# x-OSC_Gloves_v2.net
KiCad netlist of a schematic drawn in EAGLE
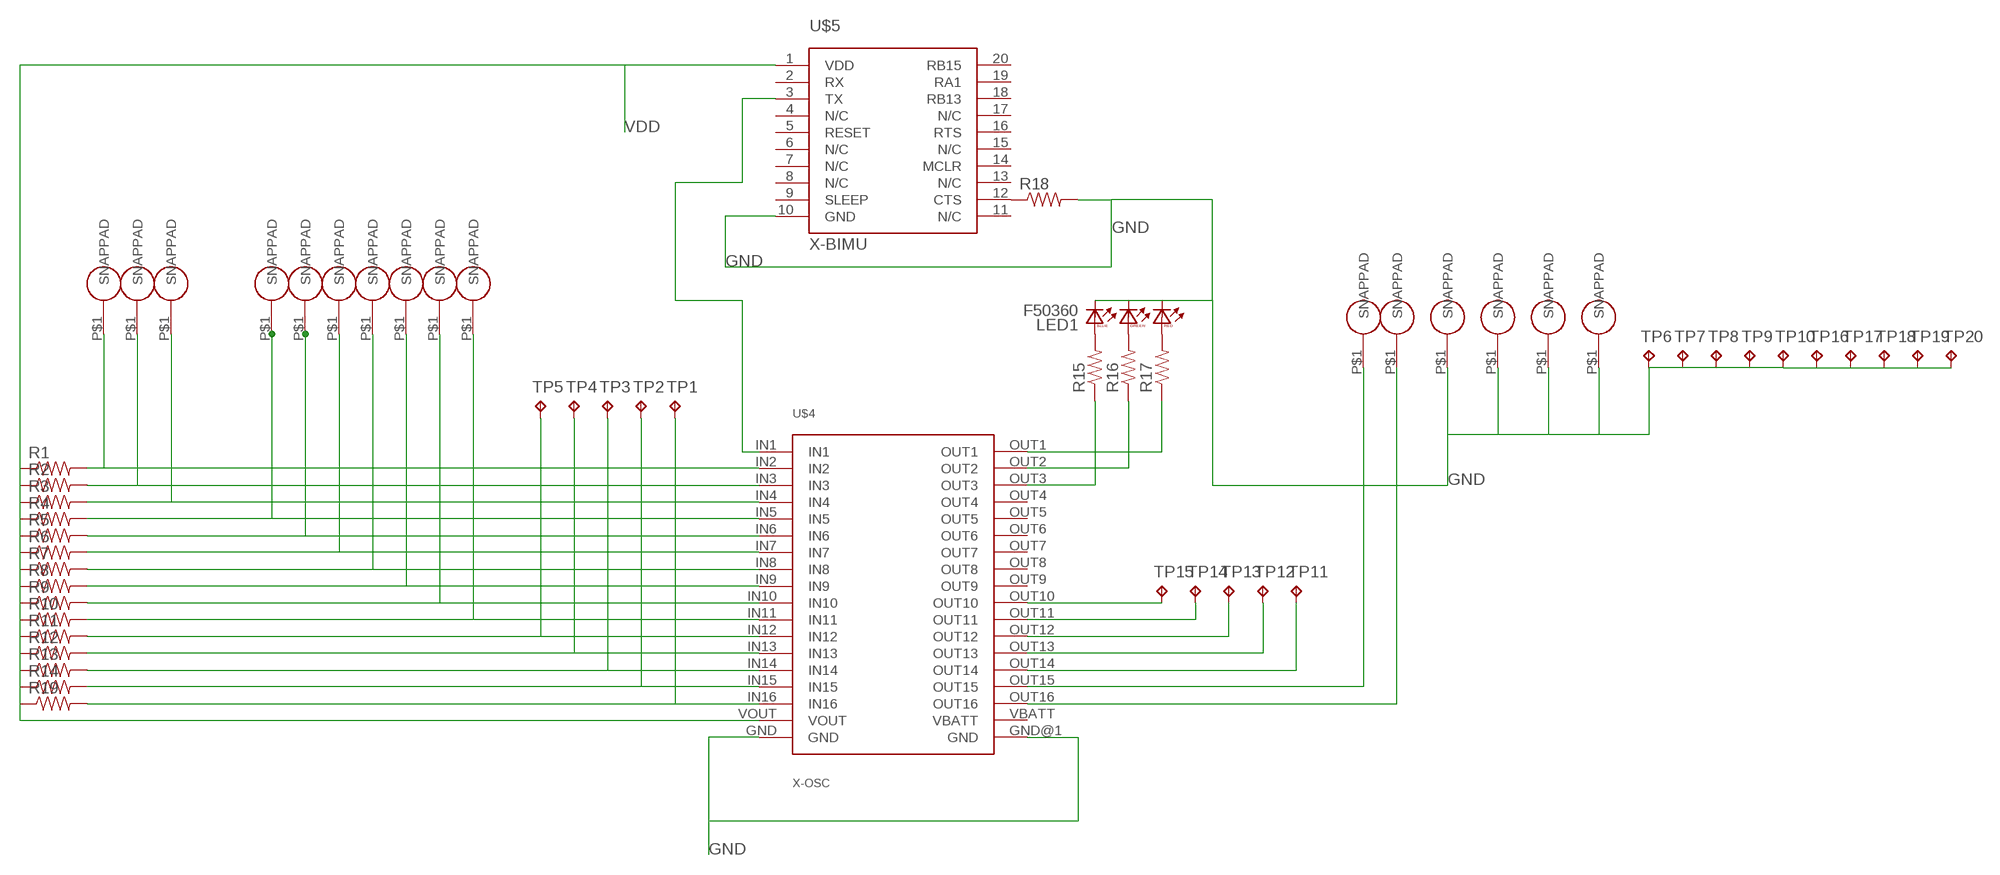
[diagram p0: schematic, sheet 1]

(export (version "E")
  (design (tool "Eeschema 10.0.6"))
  (components
    (comp (ref "LED1")
      (value "F50360")
      (footprint "eagle-import:F50360")
      (libsource (lib "eagle-import") (part "F50360"))
    )
    (comp (ref "R1")
      (value "RESISTOR0805-RES")
      (footprint "eagle-import:0805")
      (libsource (lib "eagle-import") (part "RESISTOR0805-RES"))
    )
    (comp (ref "R2")
      (value "RESISTOR0805-RES")
      (footprint "eagle-import:0805")
      (libsource (lib "eagle-import") (part "RESISTOR0805-RES"))
    )
    (comp (ref "R3")
      (value "RESISTOR0805-RES")
      (footprint "eagle-import:0805")
      (libsource (lib "eagle-import") (part "RESISTOR0805-RES"))
    )
    (comp (ref "R4")
      (value "RESISTOR0805-RES")
      (footprint "eagle-import:0805")
      (libsource (lib "eagle-import") (part "RESISTOR0805-RES"))
    )
    (comp (ref "R5")
      (value "RESISTOR0805-RES")
      (footprint "eagle-import:0805")
      (libsource (lib "eagle-import") (part "RESISTOR0805-RES"))
    )
    (comp (ref "R6")
      (value "RESISTOR0805-RES")
      (footprint "eagle-import:0805")
      (libsource (lib "eagle-import") (part "RESISTOR0805-RES"))
    )
    (comp (ref "R7")
      (value "RESISTOR0805-RES")
      (footprint "eagle-import:0805")
      (libsource (lib "eagle-import") (part "RESISTOR0805-RES"))
    )
    (comp (ref "R8")
      (value "RESISTOR0805-RES")
      (footprint "eagle-import:0805")
      (libsource (lib "eagle-import") (part "RESISTOR0805-RES"))
    )
    (comp (ref "R9")
      (value "RESISTOR0805-RES")
      (footprint "eagle-import:0805")
      (libsource (lib "eagle-import") (part "RESISTOR0805-RES"))
    )
    (comp (ref "R10")
      (value "RESISTOR0805-RES")
      (footprint "eagle-import:0805")
      (libsource (lib "eagle-import") (part "RESISTOR0805-RES"))
    )
    (comp (ref "R11")
      (value "RESISTOR0805-RES")
      (footprint "eagle-import:0805")
      (libsource (lib "eagle-import") (part "RESISTOR0805-RES"))
    )
    (comp (ref "R12")
      (value "RESISTOR0805-RES")
      (footprint "eagle-import:0805")
      (libsource (lib "eagle-import") (part "RESISTOR0805-RES"))
    )
    (comp (ref "R13")
      (value "RESISTOR0805-RES")
      (footprint "eagle-import:0805")
      (libsource (lib "eagle-import") (part "RESISTOR0805-RES"))
    )
    (comp (ref "R14")
      (value "RESISTOR0805-RES")
      (footprint "eagle-import:0805")
      (libsource (lib "eagle-import") (part "RESISTOR0805-RES"))
    )
    (comp (ref "R15")
      (value "RESISTOR0805-RES")
      (footprint "eagle-import:0805")
      (libsource (lib "eagle-import") (part "RESISTOR0805-RES"))
    )
    (comp (ref "R16")
      (value "RESISTOR0805-RES")
      (footprint "eagle-import:0805")
      (libsource (lib "eagle-import") (part "RESISTOR0805-RES"))
    )
    (comp (ref "R17")
      (value "RESISTOR0805-RES")
      (footprint "eagle-import:0805")
      (libsource (lib "eagle-import") (part "RESISTOR0805-RES"))
    )
    (comp (ref "R18")
      (value "RESISTOR0805-RES")
      (footprint "eagle-import:0805")
      (libsource (lib "eagle-import") (part "RESISTOR0805-RES"))
    )
    (comp (ref "R19")
      (value "RESISTOR0805-RES")
      (footprint "eagle-import:0805")
      (libsource (lib "eagle-import") (part "RESISTOR0805-RES"))
    )
    (comp (ref "TP1")
      (value "TPTP20R")
      (footprint "eagle-import:TP20R")
      (libsource (lib "eagle-import") (part "TPTP20R"))
    )
    (comp (ref "TP2")
      (value "TPTP20R")
      (footprint "eagle-import:TP20R")
      (libsource (lib "eagle-import") (part "TPTP20R"))
    )
    (comp (ref "TP3")
      (value "TPTP20R")
      (footprint "eagle-import:TP20R")
      (libsource (lib "eagle-import") (part "TPTP20R"))
    )
    (comp (ref "TP4")
      (value "TPTP20R")
      (footprint "eagle-import:TP20R")
      (libsource (lib "eagle-import") (part "TPTP20R"))
    )
    (comp (ref "TP5")
      (value "TPTP20R")
      (footprint "eagle-import:TP20R")
      (libsource (lib "eagle-import") (part "TPTP20R"))
    )
    (comp (ref "TP6")
      (value "TPTP20R")
      (footprint "eagle-import:TP20R")
      (libsource (lib "eagle-import") (part "TPTP20R"))
    )
    (comp (ref "TP7")
      (value "TPTP20R")
      (footprint "eagle-import:TP20R")
      (libsource (lib "eagle-import") (part "TPTP20R"))
    )
    (comp (ref "TP8")
      (value "TPTP20R")
      (footprint "eagle-import:TP20R")
      (libsource (lib "eagle-import") (part "TPTP20R"))
    )
    (comp (ref "TP9")
      (value "TPTP20R")
      (footprint "eagle-import:TP20R")
      (libsource (lib "eagle-import") (part "TPTP20R"))
    )
    (comp (ref "TP10")
      (value "TPTP20R")
      (footprint "eagle-import:TP20R")
      (libsource (lib "eagle-import") (part "TPTP20R"))
    )
    (comp (ref "TP11")
      (value "TPTP20R")
      (footprint "eagle-import:TP20R")
      (libsource (lib "eagle-import") (part "TPTP20R"))
    )
    (comp (ref "TP12")
      (value "TPTP20R")
      (footprint "eagle-import:TP20R")
      (libsource (lib "eagle-import") (part "TPTP20R"))
    )
    (comp (ref "TP13")
      (value "TPTP20R")
      (footprint "eagle-import:TP20R")
      (libsource (lib "eagle-import") (part "TPTP20R"))
    )
    (comp (ref "TP14")
      (value "TPTP20R")
      (footprint "eagle-import:TP20R")
      (libsource (lib "eagle-import") (part "TPTP20R"))
    )
    (comp (ref "TP15")
      (value "TPTP20R")
      (footprint "eagle-import:TP20R")
      (libsource (lib "eagle-import") (part "TPTP20R"))
    )
    (comp (ref "TP16")
      (value "TPTP20R")
      (footprint "eagle-import:TP20R")
      (libsource (lib "eagle-import") (part "TPTP20R"))
    )
    (comp (ref "TP17")
      (value "TPTP20R")
      (footprint "eagle-import:TP20R")
      (libsource (lib "eagle-import") (part "TPTP20R"))
    )
    (comp (ref "TP18")
      (value "TPTP20R")
      (footprint "eagle-import:TP20R")
      (libsource (lib "eagle-import") (part "TPTP20R"))
    )
    (comp (ref "TP19")
      (value "TPTP20R")
      (footprint "eagle-import:TP20R")
      (libsource (lib "eagle-import") (part "TPTP20R"))
    )
    (comp (ref "TP20")
      (value "TPTP20R")
      (footprint "eagle-import:TP20R")
      (libsource (lib "eagle-import") (part "TPTP20R"))
    )
    (comp (ref "U$1")
      (value "SNAP-PAD_7MM_ROUND")
      (footprint "eagle-import:SNAP-PAD_7MM_RD")
      (libsource (lib "eagle-import") (part "SNAP-PAD_7MM_ROUND"))
    )
    (comp (ref "U$2")
      (value "SNAP-PAD_7MM_ROUND")
      (footprint "eagle-import:SNAP-PAD_7MM_RD")
      (libsource (lib "eagle-import") (part "SNAP-PAD_7MM_ROUND"))
    )
    (comp (ref "U$3")
      (value "SNAP-PAD_7MM_ROUND")
      (footprint "eagle-import:SNAP-PAD_7MM_RD")
      (libsource (lib "eagle-import") (part "SNAP-PAD_7MM_ROUND"))
    )
    (comp (ref "U$4")
      (value "X-OSC")
      (footprint "eagle-import:X-OSC_SMD")
      (libsource (lib "eagle-import") (part "X-OSC"))
    )
    (comp (ref "U$5")
      (value "X-BIMU")
      (footprint "eagle-import:X-BIMU_SMD")
      (libsource (lib "eagle-import") (part "X-BIMU"))
    )
    (comp (ref "U$6")
      (value "SNAP-PAD_7MM_ROUND")
      (footprint "eagle-import:SNAP-PAD_7MM_RD")
      (libsource (lib "eagle-import") (part "SNAP-PAD_7MM_ROUND"))
    )
    (comp (ref "U$7")
      (value "SNAP-PAD_7MM_ROUND")
      (footprint "eagle-import:SNAP-PAD_7MM_RD")
      (libsource (lib "eagle-import") (part "SNAP-PAD_7MM_ROUND"))
    )
    (comp (ref "U$8")
      (value "SNAP-PAD_7MM_ROUND")
      (footprint "eagle-import:SNAP-PAD_7MM_RD")
      (libsource (lib "eagle-import") (part "SNAP-PAD_7MM_ROUND"))
    )
    (comp (ref "U$9")
      (value "SNAP-PAD_7MM_ROUND")
      (footprint "eagle-import:SNAP-PAD_7MM_RD")
      (libsource (lib "eagle-import") (part "SNAP-PAD_7MM_ROUND"))
    )
    (comp (ref "U$10")
      (value "SNAP-PAD_7MM_ROUND")
      (footprint "eagle-import:SNAP-PAD_7MM_RD")
      (libsource (lib "eagle-import") (part "SNAP-PAD_7MM_ROUND"))
    )
    (comp (ref "U$11")
      (value "SNAP-PAD_7MM_ROUND")
      (footprint "eagle-import:SNAP-PAD_7MM_RD")
      (libsource (lib "eagle-import") (part "SNAP-PAD_7MM_ROUND"))
    )
    (comp (ref "U$12")
      (value "SNAP-PAD_7MM_ROUND")
      (footprint "eagle-import:SNAP-PAD_7MM_RD")
      (libsource (lib "eagle-import") (part "SNAP-PAD_7MM_ROUND"))
    )
    (comp (ref "U$13")
      (value "SNAP-PAD_7MM_ROUND")
      (footprint "eagle-import:SNAP-PAD_7MM_RD")
      (libsource (lib "eagle-import") (part "SNAP-PAD_7MM_ROUND"))
    )
    (comp (ref "U$14")
      (value "SNAP-PAD_7MM_ROUND")
      (footprint "eagle-import:SNAP-PAD_7MM_RD")
      (libsource (lib "eagle-import") (part "SNAP-PAD_7MM_ROUND"))
    )
    (comp (ref "U$15")
      (value "SNAP-PAD_7MM_ROUND")
      (footprint "eagle-import:SNAP-PAD_7MM_RD")
      (libsource (lib "eagle-import") (part "SNAP-PAD_7MM_ROUND"))
    )
    (comp (ref "U$16")
      (value "SNAP-PAD_7MM_ROUND")
      (footprint "eagle-import:SNAP-PAD_7MM_RD")
      (libsource (lib "eagle-import") (part "SNAP-PAD_7MM_ROUND"))
    )
    (comp (ref "U$17")
      (value "SNAP-PAD_7MM_ROUND")
      (footprint "eagle-import:SNAP-PAD_7MM_RD")
      (libsource (lib "eagle-import") (part "SNAP-PAD_7MM_ROUND"))
    )
    (comp (ref "U$18")
      (value "SNAP-PAD_7MM_ROUND")
      (footprint "eagle-import:SNAP-PAD_7MM_RD")
      (libsource (lib "eagle-import") (part "SNAP-PAD_7MM_ROUND"))
    )
  )
  (nets
    (net (code "1") (name "/GND") (class "Default")
      (node (ref "LED1") (pin "BC") (pinfunction "BC_BC") (pintype "passive"))
      (node (ref "LED1") (pin "GC") (pinfunction "GC_GC") (pintype "passive"))
      (node (ref "LED1") (pin "RC") (pinfunction "RC_RC") (pintype "passive"))
      (node (ref "R18") (pin "2") (pinfunction "2_2") (pintype "passive"))
      (node (ref "TP10") (pin "TP") (pinfunction "TP_TP") (pintype "input"))
      (node (ref "TP16") (pin "TP") (pinfunction "TP_TP") (pintype "input"))
      (node (ref "TP17") (pin "TP") (pinfunction "TP_TP") (pintype "input"))
      (node (ref "TP18") (pin "TP") (pinfunction "TP_TP") (pintype "input"))
      (node (ref "TP19") (pin "TP") (pinfunction "TP_TP") (pintype "input"))
      (node (ref "TP20") (pin "TP") (pinfunction "TP_TP") (pintype "input"))
      (node (ref "TP6") (pin "TP") (pinfunction "TP_TP") (pintype "input"))
      (node (ref "TP7") (pin "TP") (pinfunction "TP_TP") (pintype "input"))
      (node (ref "TP8") (pin "TP") (pinfunction "TP_TP") (pintype "input"))
      (node (ref "TP9") (pin "TP") (pinfunction "TP_TP") (pintype "input"))
      (node (ref "U$15") (pin "P$1") (pinfunction "SNAPPAD_P$1") (pintype "bidirectional"))
      (node (ref "U$16") (pin "P$1") (pinfunction "SNAPPAD_P$1") (pintype "bidirectional"))
      (node (ref "U$17") (pin "P$1") (pinfunction "SNAPPAD_P$1") (pintype "bidirectional"))
      (node (ref "U$18") (pin "P$1") (pinfunction "SNAPPAD_P$1") (pintype "bidirectional"))
      (node (ref "U$4") (pin "GND") (pinfunction "GND_GND") (pintype "bidirectional"))
      (node (ref "U$4") (pin "GND@1") (pinfunction "GND_GND@1") (pintype "bidirectional"))
      (node (ref "U$5") (pin "10") (pinfunction "GND_10") (pintype "bidirectional"))
    )
    (net (code "2") (name "/VDD") (class "Default")
      (node (ref "R1") (pin "1") (pinfunction "1_1") (pintype "passive"))
      (node (ref "R10") (pin "1") (pinfunction "1_1") (pintype "passive"))
      (node (ref "R11") (pin "1") (pinfunction "1_1") (pintype "passive"))
      (node (ref "R12") (pin "1") (pinfunction "1_1") (pintype "passive"))
      (node (ref "R13") (pin "1") (pinfunction "1_1") (pintype "passive"))
      (node (ref "R14") (pin "1") (pinfunction "1_1") (pintype "passive"))
      (node (ref "R19") (pin "1") (pinfunction "1_1") (pintype "passive"))
      (node (ref "R2") (pin "1") (pinfunction "1_1") (pintype "passive"))
      (node (ref "R3") (pin "1") (pinfunction "1_1") (pintype "passive"))
      (node (ref "R4") (pin "1") (pinfunction "1_1") (pintype "passive"))
      (node (ref "R5") (pin "1") (pinfunction "1_1") (pintype "passive"))
      (node (ref "R6") (pin "1") (pinfunction "1_1") (pintype "passive"))
      (node (ref "R7") (pin "1") (pinfunction "1_1") (pintype "passive"))
      (node (ref "R8") (pin "1") (pinfunction "1_1") (pintype "passive"))
      (node (ref "R9") (pin "1") (pinfunction "1_1") (pintype "passive"))
      (node (ref "U$4") (pin "VOUT") (pinfunction "VOUT_VOUT") (pintype "bidirectional"))
      (node (ref "U$5") (pin "1") (pinfunction "VDD_1") (pintype "bidirectional"))
    )
    (net (code "3") (name "Net-(LED1-PadBA)") (class "Default")
      (node (ref "LED1") (pin "BA") (pinfunction "BA_BA") (pintype "passive"))
      (node (ref "R15") (pin "2") (pinfunction "2_2") (pintype "passive"))
    )
    (net (code "4") (name "Net-(LED1-PadGA)") (class "Default")
      (node (ref "LED1") (pin "GA") (pinfunction "GA_GA") (pintype "passive"))
      (node (ref "R16") (pin "2") (pinfunction "2_2") (pintype "passive"))
    )
    (net (code "5") (name "Net-(LED1-PadRA)") (class "Default")
      (node (ref "LED1") (pin "RA") (pinfunction "RA_RA") (pintype "passive"))
      (node (ref "R17") (pin "2") (pinfunction "2_2") (pintype "passive"))
    )
    (net (code "6") (name "Net-(R11-Pad2)") (class "Default")
      (node (ref "R11") (pin "2") (pinfunction "2_2") (pintype "passive"))
      (node (ref "TP5") (pin "TP") (pinfunction "TP_TP") (pintype "input"))
      (node (ref "U$4") (pin "IN12") (pinfunction "IN12_IN12") (pintype "bidirectional"))
    )
    (net (code "7") (name "Net-(R12-Pad2)") (class "Default")
      (node (ref "R12") (pin "2") (pinfunction "2_2") (pintype "passive"))
      (node (ref "TP4") (pin "TP") (pinfunction "TP_TP") (pintype "input"))
      (node (ref "U$4") (pin "IN13") (pinfunction "IN13_IN13") (pintype "bidirectional"))
    )
    (net (code "8") (name "Net-(R13-Pad2)") (class "Default")
      (node (ref "R13") (pin "2") (pinfunction "2_2") (pintype "passive"))
      (node (ref "TP3") (pin "TP") (pinfunction "TP_TP") (pintype "input"))
      (node (ref "U$4") (pin "IN14") (pinfunction "IN14_IN14") (pintype "bidirectional"))
    )
    (net (code "9") (name "Net-(R14-Pad2)") (class "Default")
      (node (ref "R14") (pin "2") (pinfunction "2_2") (pintype "passive"))
      (node (ref "TP2") (pin "TP") (pinfunction "TP_TP") (pintype "input"))
      (node (ref "U$4") (pin "IN15") (pinfunction "IN15_IN15") (pintype "bidirectional"))
    )
    (net (code "10") (name "Net-(R15-Pad1)") (class "Default")
      (node (ref "R15") (pin "1") (pinfunction "1_1") (pintype "passive"))
      (node (ref "U$4") (pin "OUT3") (pinfunction "OUT3_OUT3") (pintype "bidirectional"))
    )
    (net (code "11") (name "Net-(R16-Pad1)") (class "Default")
      (node (ref "R16") (pin "1") (pinfunction "1_1") (pintype "passive"))
      (node (ref "U$4") (pin "OUT2") (pinfunction "OUT2_OUT2") (pintype "bidirectional"))
    )
    (net (code "12") (name "Net-(R17-Pad1)") (class "Default")
      (node (ref "R17") (pin "1") (pinfunction "1_1") (pintype "passive"))
      (node (ref "U$4") (pin "OUT1") (pinfunction "OUT1_OUT1") (pintype "bidirectional"))
    )
    (net (code "13") (name "Net-(R19-Pad2)") (class "Default")
      (node (ref "R19") (pin "2") (pinfunction "2_2") (pintype "passive"))
      (node (ref "TP1") (pin "TP") (pinfunction "TP_TP") (pintype "input"))
      (node (ref "U$4") (pin "IN16") (pinfunction "IN16_IN16") (pintype "bidirectional"))
    )
    (net (code "14") (name "Net-(TP11-PadTP)") (class "Default")
      (node (ref "TP11") (pin "TP") (pinfunction "TP_TP") (pintype "input"))
      (node (ref "U$4") (pin "OUT14") (pinfunction "OUT14_OUT14") (pintype "bidirectional"))
    )
    (net (code "15") (name "Net-(TP12-PadTP)") (class "Default")
      (node (ref "TP12") (pin "TP") (pinfunction "TP_TP") (pintype "input"))
      (node (ref "U$4") (pin "OUT13") (pinfunction "OUT13_OUT13") (pintype "bidirectional"))
    )
    (net (code "16") (name "Net-(TP13-PadTP)") (class "Default")
      (node (ref "TP13") (pin "TP") (pinfunction "TP_TP") (pintype "input"))
      (node (ref "U$4") (pin "OUT12") (pinfunction "OUT12_OUT12") (pintype "bidirectional"))
    )
    (net (code "17") (name "Net-(TP14-PadTP)") (class "Default")
      (node (ref "TP14") (pin "TP") (pinfunction "TP_TP") (pintype "input"))
      (node (ref "U$4") (pin "OUT11") (pinfunction "OUT11_OUT11") (pintype "bidirectional"))
    )
    (net (code "18") (name "Net-(TP15-PadTP)") (class "Default")
      (node (ref "TP15") (pin "TP") (pinfunction "TP_TP") (pintype "input"))
      (node (ref "U$4") (pin "OUT10") (pinfunction "OUT10_OUT10") (pintype "bidirectional"))
    )
    (net (code "19") (name "Net-(U$1-SNAPPAD)") (class "Default")
      (node (ref "R1") (pin "2") (pinfunction "2_2") (pintype "passive"))
      (node (ref "U$1") (pin "P$1") (pinfunction "SNAPPAD_P$1") (pintype "bidirectional"))
      (node (ref "U$4") (pin "IN2") (pinfunction "IN2_IN2") (pintype "bidirectional"))
    )
    (net (code "20") (name "Net-(U$2-SNAPPAD)") (class "Default")
      (node (ref "R2") (pin "2") (pinfunction "2_2") (pintype "passive"))
      (node (ref "U$2") (pin "P$1") (pinfunction "SNAPPAD_P$1") (pintype "bidirectional"))
      (node (ref "U$4") (pin "IN3") (pinfunction "IN3_IN3") (pintype "bidirectional"))
    )
    (net (code "21") (name "Net-(U$3-SNAPPAD)") (class "Default")
      (node (ref "R3") (pin "2") (pinfunction "2_2") (pintype "passive"))
      (node (ref "U$3") (pin "P$1") (pinfunction "SNAPPAD_P$1") (pintype "bidirectional"))
      (node (ref "U$4") (pin "IN4") (pinfunction "IN4_IN4") (pintype "bidirectional"))
    )
    (net (code "22") (name "Net-(U$5-CTS)") (class "Default")
      (node (ref "R18") (pin "1") (pinfunction "1_1") (pintype "passive"))
      (node (ref "U$5") (pin "12") (pinfunction "CTS_12") (pintype "bidirectional"))
    )
    (net (code "23") (name "Net-(U$5-TX)") (class "Default")
      (node (ref "U$4") (pin "IN1") (pinfunction "IN1_IN1") (pintype "bidirectional"))
      (node (ref "U$5") (pin "3") (pinfunction "TX_3") (pintype "bidirectional"))
    )
    (net (code "24") (name "Net-(U$6-SNAPPAD)") (class "Default")
      (node (ref "R4") (pin "2") (pinfunction "2_2") (pintype "passive"))
      (node (ref "U$4") (pin "IN5") (pinfunction "IN5_IN5") (pintype "bidirectional"))
      (node (ref "U$6") (pin "P$1") (pinfunction "SNAPPAD_P$1") (pintype "bidirectional"))
    )
    (net (code "25") (name "Net-(U$7-SNAPPAD)") (class "Default")
      (node (ref "R5") (pin "2") (pinfunction "2_2") (pintype "passive"))
      (node (ref "U$4") (pin "IN6") (pinfunction "IN6_IN6") (pintype "bidirectional"))
      (node (ref "U$7") (pin "P$1") (pinfunction "SNAPPAD_P$1") (pintype "bidirectional"))
    )
    (net (code "26") (name "Net-(U$8-SNAPPAD)") (class "Default")
      (node (ref "R6") (pin "2") (pinfunction "2_2") (pintype "passive"))
      (node (ref "U$4") (pin "IN7") (pinfunction "IN7_IN7") (pintype "bidirectional"))
      (node (ref "U$8") (pin "P$1") (pinfunction "SNAPPAD_P$1") (pintype "bidirectional"))
    )
    (net (code "27") (name "Net-(U$9-SNAPPAD)") (class "Default")
      (node (ref "R7") (pin "2") (pinfunction "2_2") (pintype "passive"))
      (node (ref "U$4") (pin "IN8") (pinfunction "IN8_IN8") (pintype "bidirectional"))
      (node (ref "U$9") (pin "P$1") (pinfunction "SNAPPAD_P$1") (pintype "bidirectional"))
    )
    (net (code "28") (name "Net-(U$10-SNAPPAD)") (class "Default")
      (node (ref "R8") (pin "2") (pinfunction "2_2") (pintype "passive"))
      (node (ref "U$10") (pin "P$1") (pinfunction "SNAPPAD_P$1") (pintype "bidirectional"))
      (node (ref "U$4") (pin "IN9") (pinfunction "IN9_IN9") (pintype "bidirectional"))
    )
    (net (code "29") (name "Net-(U$11-SNAPPAD)") (class "Default")
      (node (ref "R9") (pin "2") (pinfunction "2_2") (pintype "passive"))
      (node (ref "U$11") (pin "P$1") (pinfunction "SNAPPAD_P$1") (pintype "bidirectional"))
      (node (ref "U$4") (pin "IN10") (pinfunction "IN10_IN10") (pintype "bidirectional"))
    )
    (net (code "30") (name "Net-(U$12-SNAPPAD)") (class "Default")
      (node (ref "R10") (pin "2") (pinfunction "2_2") (pintype "passive"))
      (node (ref "U$12") (pin "P$1") (pinfunction "SNAPPAD_P$1") (pintype "bidirectional"))
      (node (ref "U$4") (pin "IN11") (pinfunction "IN11_IN11") (pintype "bidirectional"))
    )
    (net (code "31") (name "Net-(U$13-SNAPPAD)") (class "Default")
      (node (ref "U$13") (pin "P$1") (pinfunction "SNAPPAD_P$1") (pintype "bidirectional"))
      (node (ref "U$4") (pin "OUT15") (pinfunction "OUT15_OUT15") (pintype "bidirectional"))
    )
    (net (code "32") (name "Net-(U$14-SNAPPAD)") (class "Default")
      (node (ref "U$14") (pin "P$1") (pinfunction "SNAPPAD_P$1") (pintype "bidirectional"))
      (node (ref "U$4") (pin "OUT16") (pinfunction "OUT16_OUT16") (pintype "bidirectional"))
    )
    (net (code "33") (name "unconnected-(U$4-PadOUT4)") (class "Default")
      (node (ref "U$4") (pin "OUT4") (pinfunction "OUT4_OUT4") (pintype "bidirectional"))
    )
    (net (code "34") (name "unconnected-(U$4-PadOUT5)") (class "Default")
      (node (ref "U$4") (pin "OUT5") (pinfunction "OUT5_OUT5") (pintype "bidirectional"))
    )
    (net (code "35") (name "unconnected-(U$4-PadOUT6)") (class "Default")
      (node (ref "U$4") (pin "OUT6") (pinfunction "OUT6_OUT6") (pintype "bidirectional"))
    )
    (net (code "36") (name "unconnected-(U$4-PadOUT7)") (class "Default")
      (node (ref "U$4") (pin "OUT7") (pinfunction "OUT7_OUT7") (pintype "bidirectional"))
    )
    (net (code "37") (name "unconnected-(U$4-PadOUT8)") (class "Default")
      (node (ref "U$4") (pin "OUT8") (pinfunction "OUT8_OUT8") (pintype "bidirectional"))
    )
    (net (code "38") (name "unconnected-(U$4-PadOUT9)") (class "Default")
      (node (ref "U$4") (pin "OUT9") (pinfunction "OUT9_OUT9") (pintype "bidirectional"))
    )
    (net (code "39") (name "unconnected-(U$4-PadVBATT)") (class "Default")
      (node (ref "U$4") (pin "VBATT") (pinfunction "VBATT_VBATT") (pintype "bidirectional"))
    )
    (net (code "40") (name "unconnected-(U$5-MCLR-Pad14)") (class "Default")
      (node (ref "U$5") (pin "14") (pinfunction "MCLR_14") (pintype "bidirectional"))
    )
    (net (code "41") (name "unconnected-(U$5-N{slash}C-Pad4)") (class "Default")
      (node (ref "U$5") (pin "4") (pinfunction "N/C_4") (pintype "bidirectional"))
    )
    (net (code "42") (name "unconnected-(U$5-N{slash}C-Pad6)") (class "Default")
      (node (ref "U$5") (pin "6") (pinfunction "N/C_6") (pintype "bidirectional"))
    )
    (net (code "43") (name "unconnected-(U$5-N{slash}C-Pad7)") (class "Default")
      (node (ref "U$5") (pin "7") (pinfunction "N/C_7") (pintype "bidirectional"))
    )
    (net (code "44") (name "unconnected-(U$5-N{slash}C-Pad8)") (class "Default")
      (node (ref "U$5") (pin "8") (pinfunction "N/C_8") (pintype "bidirectional"))
    )
    (net (code "45") (name "unconnected-(U$5-N{slash}C-Pad11)") (class "Default")
      (node (ref "U$5") (pin "11") (pinfunction "N/C_11") (pintype "bidirectional"))
    )
    (net (code "46") (name "unconnected-(U$5-N{slash}C-Pad13)") (class "Default")
      (node (ref "U$5") (pin "13") (pinfunction "N/C_13") (pintype "bidirectional"))
    )
    (net (code "47") (name "unconnected-(U$5-N{slash}C-Pad15)") (class "Default")
      (node (ref "U$5") (pin "15") (pinfunction "N/C_15") (pintype "bidirectional"))
    )
    (net (code "48") (name "unconnected-(U$5-N{slash}C-Pad17)") (class "Default")
      (node (ref "U$5") (pin "17") (pinfunction "N/C_17") (pintype "bidirectional"))
    )
    (net (code "49") (name "unconnected-(U$5-RA1-Pad19)") (class "Default")
      (node (ref "U$5") (pin "19") (pinfunction "RA1_19") (pintype "bidirectional"))
    )
    (net (code "50") (name "unconnected-(U$5-RB13-Pad18)") (class "Default")
      (node (ref "U$5") (pin "18") (pinfunction "RB13_18") (pintype "bidirectional"))
    )
    (net (code "51") (name "unconnected-(U$5-RB15-Pad20)") (class "Default")
      (node (ref "U$5") (pin "20") (pinfunction "RB15_20") (pintype "bidirectional"))
    )
    (net (code "52") (name "unconnected-(U$5-RESET-Pad5)") (class "Default")
      (node (ref "U$5") (pin "5") (pinfunction "RESET_5") (pintype "bidirectional"))
    )
    (net (code "53") (name "unconnected-(U$5-RTS-Pad16)") (class "Default")
      (node (ref "U$5") (pin "16") (pinfunction "RTS_16") (pintype "bidirectional"))
    )
    (net (code "54") (name "unconnected-(U$5-RX-Pad2)") (class "Default")
      (node (ref "U$5") (pin "2") (pinfunction "RX_2") (pintype "bidirectional"))
    )
    (net (code "55") (name "unconnected-(U$5-SLEEP-Pad9)") (class "Default")
      (node (ref "U$5") (pin "9") (pinfunction "SLEEP_9") (pintype "bidirectional"))
    )
  )
)
